# HUD_Display.net
KiCad netlist of a schematic drawn in EAGLE
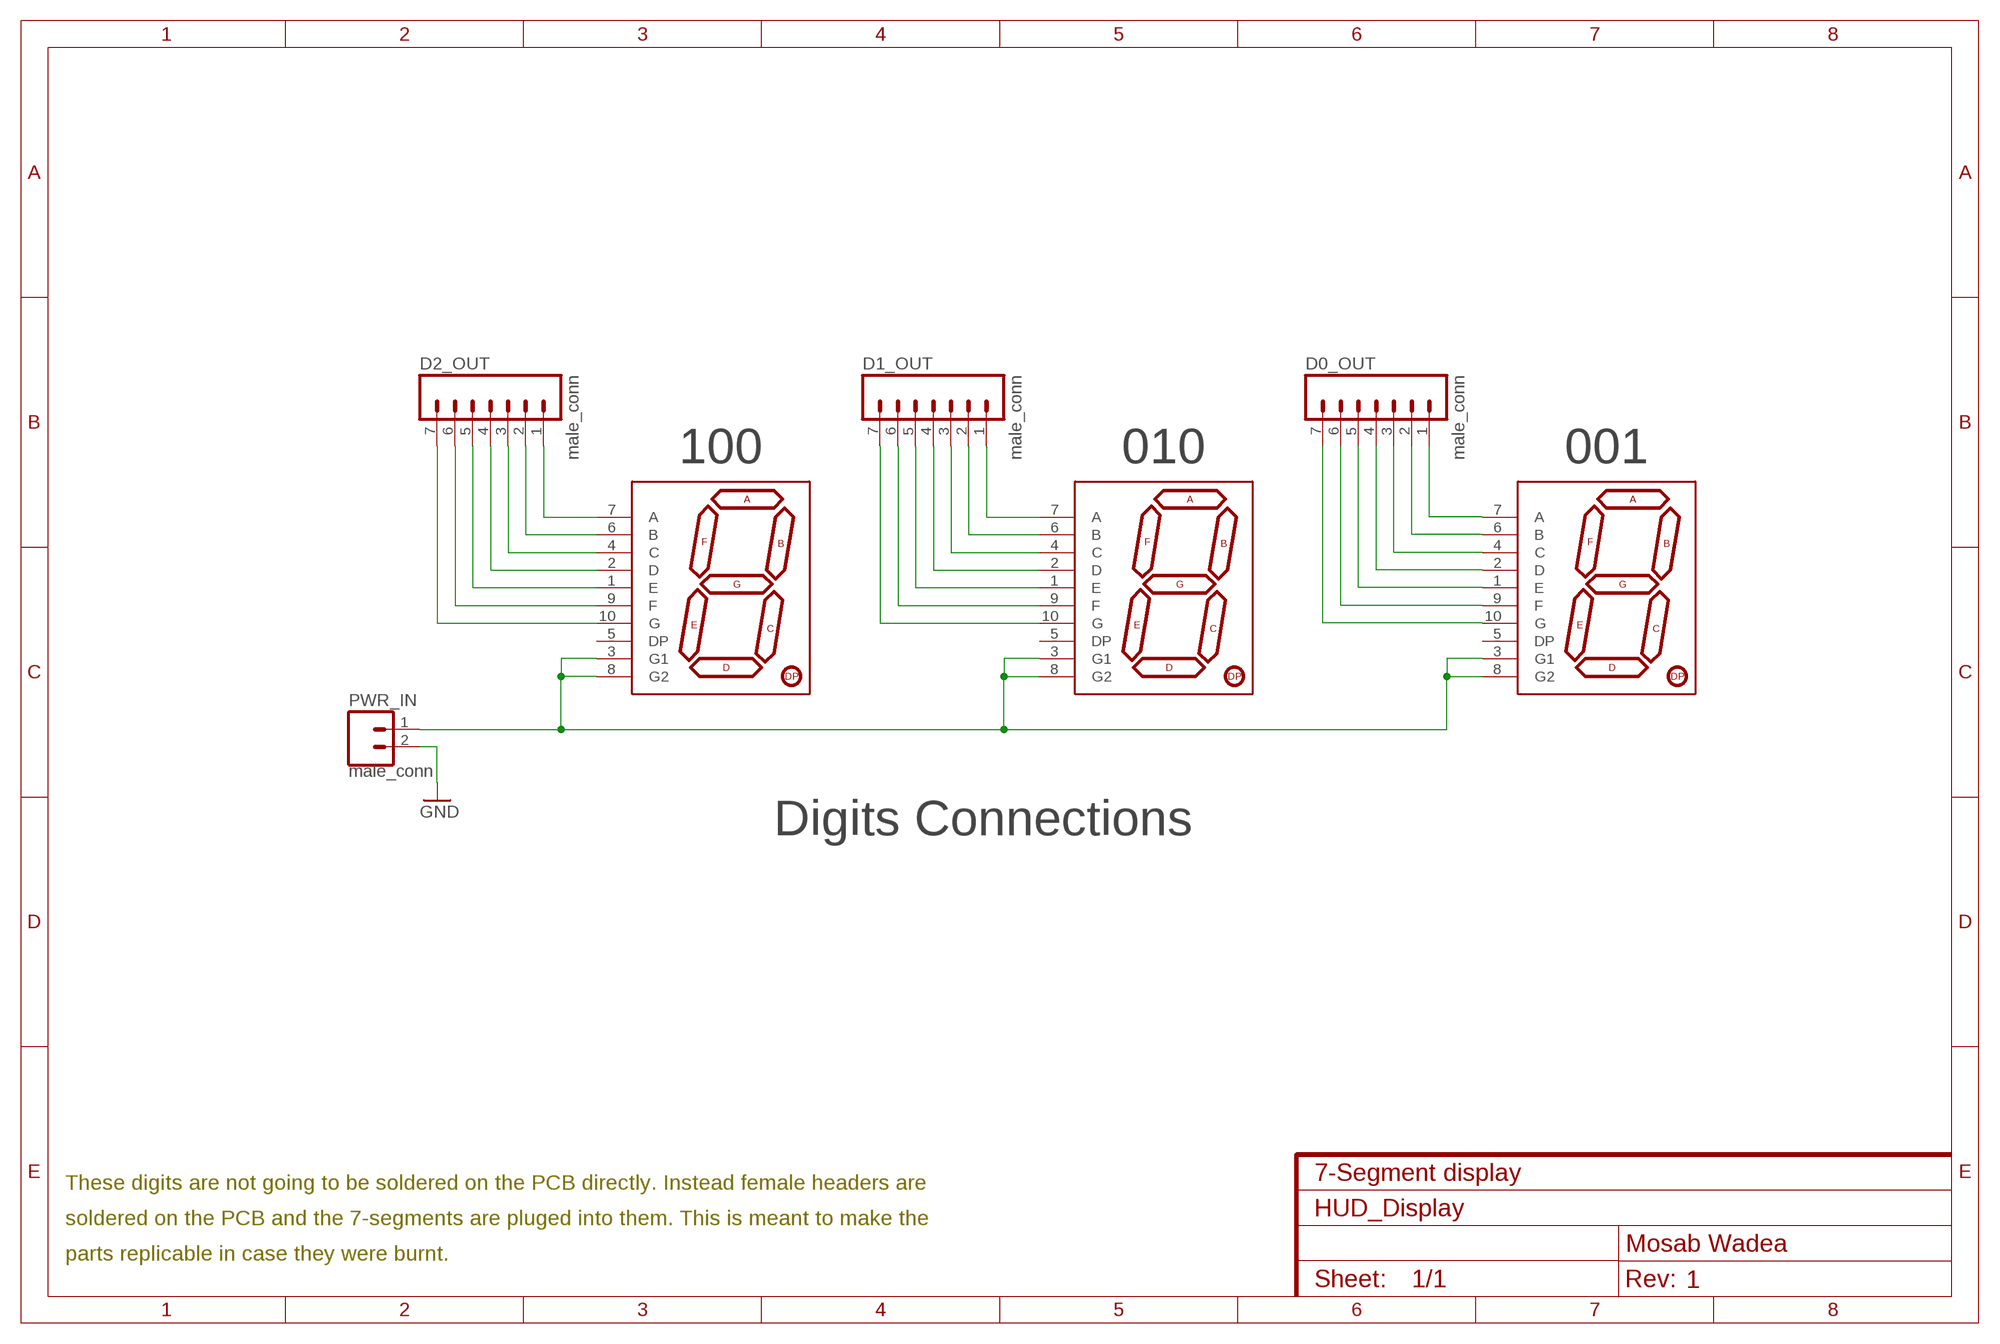
[diagram p0: schematic, sheet 1]

(export (version "E")
  (design (tool "Eeschema 10.0.6"))
  (components
    (comp (ref "D0")
      (value "7-SEGMENT-DISPLAY-1\"-REDEZ")
      (footprint "eagle-import:7-SEGMENT-1_PTH-EZ")
      (libsource (lib "eagle-import") (part "7-SEGMENT-DISPLAY-1{dblquote}-REDEZ"))
    )
    (comp (ref "D0_OUT")
      (value "male_conn")
      (footprint "eagle-import:1X07")
      (libsource (lib "eagle-import") (part "M07"))
    )
    (comp (ref "D1")
      (value "7-SEGMENT-DISPLAY-1\"-REDEZ")
      (footprint "eagle-import:7-SEGMENT-1_PTH-EZ")
      (libsource (lib "eagle-import") (part "7-SEGMENT-DISPLAY-1{dblquote}-REDEZ"))
    )
    (comp (ref "D1_OUT")
      (value "male_conn")
      (footprint "eagle-import:1X07")
      (libsource (lib "eagle-import") (part "M07"))
    )
    (comp (ref "D2")
      (value "7-SEGMENT-DISPLAY-1\"-REDEZ")
      (footprint "eagle-import:7-SEGMENT-1_PTH-EZ")
      (libsource (lib "eagle-import") (part "7-SEGMENT-DISPLAY-1{dblquote}-REDEZ"))
    )
    (comp (ref "D2_OUT")
      (value "male_conn")
      (footprint "eagle-import:1X07")
      (libsource (lib "eagle-import") (part "M07"))
    )
    (comp (ref "PWR_IN")
      (value "male_conn")
      (footprint "eagle-import:1X02")
      (libsource (lib "eagle-import") (part "M02PTH"))
    )
  )
  (nets
    (net (code "1") (name "GND") (class "Default")
      (node (ref "PWR_IN") (pin "2") (pinfunction "2_2") (pintype "passive"))
    )
    (net (code "2") (name "Net-(D0-A)") (class "Default")
      (node (ref "D0") (pin "7") (pinfunction "A_7") (pintype "bidirectional"))
      (node (ref "D0_OUT") (pin "1") (pinfunction "1_1") (pintype "passive"))
    )
    (net (code "3") (name "Net-(D0-B)") (class "Default")
      (node (ref "D0") (pin "6") (pinfunction "B_6") (pintype "bidirectional"))
      (node (ref "D0_OUT") (pin "2") (pinfunction "2_2") (pintype "passive"))
    )
    (net (code "4") (name "Net-(D0-C)") (class "Default")
      (node (ref "D0") (pin "4") (pinfunction "C_4") (pintype "bidirectional"))
      (node (ref "D0_OUT") (pin "3") (pinfunction "3_3") (pintype "passive"))
    )
    (net (code "5") (name "Net-(D0-D)") (class "Default")
      (node (ref "D0") (pin "2") (pinfunction "D_2") (pintype "bidirectional"))
      (node (ref "D0_OUT") (pin "4") (pinfunction "4_4") (pintype "passive"))
    )
    (net (code "6") (name "Net-(D0-E)") (class "Default")
      (node (ref "D0") (pin "1") (pinfunction "E_1") (pintype "bidirectional"))
      (node (ref "D0_OUT") (pin "5") (pinfunction "5_5") (pintype "passive"))
    )
    (net (code "7") (name "Net-(D0-F)") (class "Default")
      (node (ref "D0") (pin "9") (pinfunction "F_9") (pintype "bidirectional"))
      (node (ref "D0_OUT") (pin "6") (pinfunction "6_6") (pintype "passive"))
    )
    (net (code "8") (name "Net-(D0-G)") (class "Default")
      (node (ref "D0") (pin "10") (pinfunction "G_10") (pintype "bidirectional"))
      (node (ref "D0_OUT") (pin "7") (pinfunction "7_7") (pintype "passive"))
    )
    (net (code "9") (name "Net-(D0-G1)") (class "Default")
      (node (ref "D0") (pin "3") (pinfunction "G1_3") (pintype "bidirectional"))
      (node (ref "D0") (pin "8") (pinfunction "G2_8") (pintype "bidirectional"))
      (node (ref "D1") (pin "3") (pinfunction "G1_3") (pintype "bidirectional"))
      (node (ref "D1") (pin "8") (pinfunction "G2_8") (pintype "bidirectional"))
      (node (ref "D2") (pin "3") (pinfunction "G1_3") (pintype "bidirectional"))
      (node (ref "D2") (pin "8") (pinfunction "G2_8") (pintype "bidirectional"))
      (node (ref "PWR_IN") (pin "1") (pinfunction "1_1") (pintype "passive"))
    )
    (net (code "10") (name "Net-(D1-A)") (class "Default")
      (node (ref "D1") (pin "7") (pinfunction "A_7") (pintype "bidirectional"))
      (node (ref "D1_OUT") (pin "1") (pinfunction "1_1") (pintype "passive"))
    )
    (net (code "11") (name "Net-(D1-B)") (class "Default")
      (node (ref "D1") (pin "6") (pinfunction "B_6") (pintype "bidirectional"))
      (node (ref "D1_OUT") (pin "2") (pinfunction "2_2") (pintype "passive"))
    )
    (net (code "12") (name "Net-(D1-C)") (class "Default")
      (node (ref "D1") (pin "4") (pinfunction "C_4") (pintype "bidirectional"))
      (node (ref "D1_OUT") (pin "3") (pinfunction "3_3") (pintype "passive"))
    )
    (net (code "13") (name "Net-(D1-D)") (class "Default")
      (node (ref "D1") (pin "2") (pinfunction "D_2") (pintype "bidirectional"))
      (node (ref "D1_OUT") (pin "4") (pinfunction "4_4") (pintype "passive"))
    )
    (net (code "14") (name "Net-(D1-E)") (class "Default")
      (node (ref "D1") (pin "1") (pinfunction "E_1") (pintype "bidirectional"))
      (node (ref "D1_OUT") (pin "5") (pinfunction "5_5") (pintype "passive"))
    )
    (net (code "15") (name "Net-(D1-F)") (class "Default")
      (node (ref "D1") (pin "9") (pinfunction "F_9") (pintype "bidirectional"))
      (node (ref "D1_OUT") (pin "6") (pinfunction "6_6") (pintype "passive"))
    )
    (net (code "16") (name "Net-(D1-G)") (class "Default")
      (node (ref "D1") (pin "10") (pinfunction "G_10") (pintype "bidirectional"))
      (node (ref "D1_OUT") (pin "7") (pinfunction "7_7") (pintype "passive"))
    )
    (net (code "17") (name "Net-(D2-A)") (class "Default")
      (node (ref "D2") (pin "7") (pinfunction "A_7") (pintype "bidirectional"))
      (node (ref "D2_OUT") (pin "1") (pinfunction "1_1") (pintype "passive"))
    )
    (net (code "18") (name "Net-(D2-B)") (class "Default")
      (node (ref "D2") (pin "6") (pinfunction "B_6") (pintype "bidirectional"))
      (node (ref "D2_OUT") (pin "2") (pinfunction "2_2") (pintype "passive"))
    )
    (net (code "19") (name "Net-(D2-C)") (class "Default")
      (node (ref "D2") (pin "4") (pinfunction "C_4") (pintype "bidirectional"))
      (node (ref "D2_OUT") (pin "3") (pinfunction "3_3") (pintype "passive"))
    )
    (net (code "20") (name "Net-(D2-D)") (class "Default")
      (node (ref "D2") (pin "2") (pinfunction "D_2") (pintype "bidirectional"))
      (node (ref "D2_OUT") (pin "4") (pinfunction "4_4") (pintype "passive"))
    )
    (net (code "21") (name "Net-(D2-E)") (class "Default")
      (node (ref "D2") (pin "1") (pinfunction "E_1") (pintype "bidirectional"))
      (node (ref "D2_OUT") (pin "5") (pinfunction "5_5") (pintype "passive"))
    )
    (net (code "22") (name "Net-(D2-F)") (class "Default")
      (node (ref "D2") (pin "9") (pinfunction "F_9") (pintype "bidirectional"))
      (node (ref "D2_OUT") (pin "6") (pinfunction "6_6") (pintype "passive"))
    )
    (net (code "23") (name "Net-(D2-G)") (class "Default")
      (node (ref "D2") (pin "10") (pinfunction "G_10") (pintype "bidirectional"))
      (node (ref "D2_OUT") (pin "7") (pinfunction "7_7") (pintype "passive"))
    )
    (net (code "24") (name "unconnected-(D0-DP-Pad5)") (class "Default")
      (node (ref "D0") (pin "5") (pinfunction "DP_5") (pintype "bidirectional"))
    )
    (net (code "25") (name "unconnected-(D1-DP-Pad5)") (class "Default")
      (node (ref "D1") (pin "5") (pinfunction "DP_5") (pintype "bidirectional"))
    )
    (net (code "26") (name "unconnected-(D2-DP-Pad5)") (class "Default")
      (node (ref "D2") (pin "5") (pinfunction "DP_5") (pintype "bidirectional"))
    )
  )
)
